# glove_motor_dr.net
KiCad netlist of a schematic drawn in EAGLE
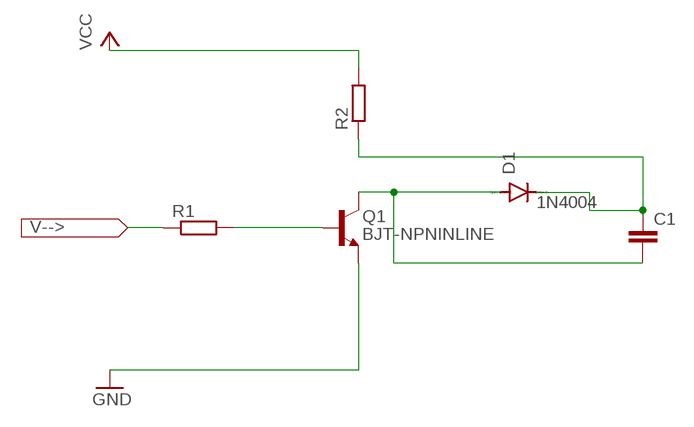
[diagram p0: schematic, sheet 1]

(export (version "E")
  (design (tool "Eeschema 10.0.6"))
  (components
    (comp (ref "C1")
      (value "C-EU025-024X044")
      (footprint "eagle-import:C025-024X044")
      (libsource (lib "eagle-import") (part "C-EU025-024X044"))
    )
    (comp (ref "D1")
      (value "1N4004")
      (footprint "eagle-import:DO41-10")
      (libsource (lib "eagle-import") (part "1N4004"))
    )
    (comp (ref "Q1")
      (value "BJT-NPNINLINE")
      (footprint "eagle-import:TO92I")
      (libsource (lib "eagle-import") (part "BJT-NPNINLINE"))
    )
    (comp (ref "R1")
      (value "R-EU_0207/7")
      (footprint "eagle-import:0207_7")
      (libsource (lib "eagle-import") (part "R-EU_0207/7"))
    )
    (comp (ref "R2")
      (value "R-EU_0207/7")
      (footprint "eagle-import:0207_7")
      (libsource (lib "eagle-import") (part "R-EU_0207/7"))
    )
  )
  (nets
    (net (code "1") (name "GND") (class "Default")
      (node (ref "Q1") (pin "E") (pinfunction "E_E") (pintype "passive"))
    )
    (net (code "2") (name "Net-(C1-Pad1)") (class "Default")
      (node (ref "C1") (pin "1") (pinfunction "1_1") (pintype "passive"))
      (node (ref "D1") (pin "C") (pinfunction "C_C") (pintype "passive"))
      (node (ref "R2") (pin "1") (pinfunction "1_1") (pintype "passive"))
    )
    (net (code "3") (name "Net-(C1-Pad2)") (class "Default")
      (node (ref "C1") (pin "2") (pinfunction "2_2") (pintype "passive"))
      (node (ref "D1") (pin "A") (pinfunction "A_A") (pintype "passive"))
      (node (ref "Q1") (pin "C") (pinfunction "C_C") (pintype "passive"))
    )
    (net (code "4") (name "Net-(Q1-PadB)") (class "Default")
      (node (ref "Q1") (pin "B") (pinfunction "B_B") (pintype "passive"))
      (node (ref "R1") (pin "2") (pinfunction "2_2") (pintype "passive"))
    )
    (net (code "5") (name "VCC") (class "Default")
      (node (ref "R2") (pin "2") (pinfunction "2_2") (pintype "passive"))
    )
    (net (code "6") (name "unconnected-(R1-Pad1)") (class "Default")
      (node (ref "R1") (pin "1") (pinfunction "1_1") (pintype "passive"))
    )
  )
)
